# DVI_D_In.net
KiCad netlist of a schematic drawn in Altium Designer
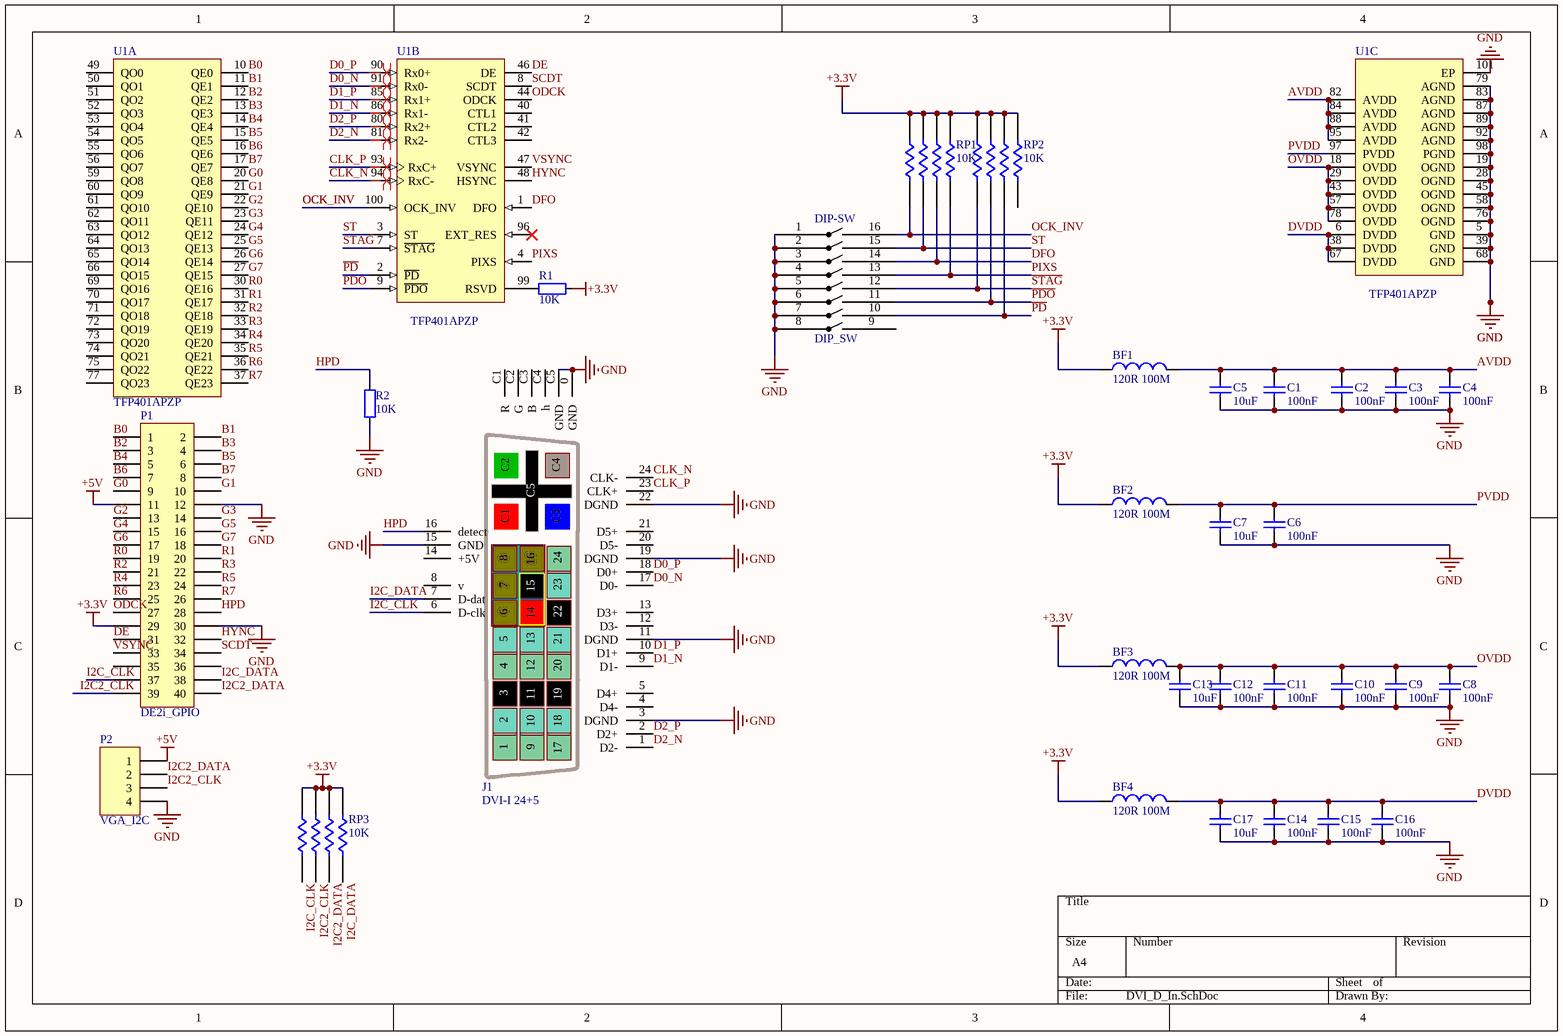
[diagram p0: DVI_D_In.SchDoc]

(export (version "E")
  (design (tool "Eeschema 10.0.6"))
  (components
    (comp (ref "BF1")
      (value "120R 100M")
      (footprint "L-1608[0603]")
      (fields (field (name "Comment") "GZ1608D121TF") (field (name "PUBLISHER") "Altium Limited"))
      (libsource (lib "Miscellaneous Devices") (part "Inductor"))
    )
    (comp (ref "BF2")
      (value "120R 100M")
      (footprint "L-1608[0603]")
      (fields (field (name "Comment") "GZ1608D121TF") (field (name "PUBLISHER") "Altium Limited"))
      (libsource (lib "Miscellaneous Devices") (part "Inductor"))
    )
    (comp (ref "BF3")
      (value "120R 100M")
      (footprint "L-1608[0603]")
      (fields (field (name "Comment") "GZ1608D121TF") (field (name "PUBLISHER") "Altium Limited"))
      (libsource (lib "Miscellaneous Devices") (part "Inductor"))
    )
    (comp (ref "BF4")
      (value "120R 100M")
      (footprint "L-1608[0603]")
      (fields (field (name "Comment") "GZ1608D121TF") (field (name "PUBLISHER") "Altium Limited"))
      (libsource (lib "Miscellaneous Devices") (part "Inductor"))
    )
    (comp (ref "C1")
      (value "100nF")
      (footprint "C-1608[0603]")
      (description "Capacitor (Semiconductor SIM Model)")
      (fields (field (name "Comment") "Cap Semi") (field (name "PUBLISHER") "Altium Limited"))
      (libsource (lib "Miscellaneous Devices") (part "Cap Semi"))
    )
    (comp (ref "C2")
      (value "100nF")
      (footprint "C-1608[0603]")
      (description "Capacitor (Semiconductor SIM Model)")
      (fields (field (name "Comment") "Cap Semi") (field (name "PUBLISHER") "Altium Limited"))
      (libsource (lib "Miscellaneous Devices") (part "Cap Semi"))
    )
    (comp (ref "C3")
      (value "100nF")
      (footprint "C-1608[0603]")
      (description "Capacitor (Semiconductor SIM Model)")
      (fields (field (name "Comment") "Cap Semi") (field (name "PUBLISHER") "Altium Limited"))
      (libsource (lib "Miscellaneous Devices") (part "Cap Semi"))
    )
    (comp (ref "C4")
      (value "100nF")
      (footprint "C-1608[0603]")
      (description "Capacitor (Semiconductor SIM Model)")
      (fields (field (name "Comment") "Cap Semi") (field (name "PUBLISHER") "Altium Limited"))
      (libsource (lib "Miscellaneous Devices") (part "Cap Semi"))
    )
    (comp (ref "C5")
      (value "10uF")
      (footprint "C-1608[0603]")
      (description "Capacitor (Semiconductor SIM Model)")
      (fields (field (name "Comment") "Cap Semi") (field (name "PUBLISHER") "Altium Limited"))
      (libsource (lib "Miscellaneous Devices") (part "Cap Semi"))
    )
    (comp (ref "C6")
      (value "100nF")
      (footprint "C-1608[0603]")
      (description "Capacitor (Semiconductor SIM Model)")
      (fields (field (name "Comment") "Cap Semi") (field (name "PUBLISHER") "Altium Limited"))
      (libsource (lib "Miscellaneous Devices") (part "Cap Semi"))
    )
    (comp (ref "C7")
      (value "10uF")
      (footprint "C-1608[0603]")
      (description "Capacitor (Semiconductor SIM Model)")
      (fields (field (name "Comment") "Cap Semi") (field (name "PUBLISHER") "Altium Limited"))
      (libsource (lib "Miscellaneous Devices") (part "Cap Semi"))
    )
    (comp (ref "C8")
      (value "100nF")
      (footprint "C-1608[0603]")
      (description "Capacitor (Semiconductor SIM Model)")
      (fields (field (name "Comment") "Cap Semi") (field (name "PUBLISHER") "Altium Limited"))
      (libsource (lib "Miscellaneous Devices") (part "Cap Semi"))
    )
    (comp (ref "C9")
      (value "100nF")
      (footprint "C-1608[0603]")
      (description "Capacitor (Semiconductor SIM Model)")
      (fields (field (name "Comment") "Cap Semi") (field (name "PUBLISHER") "Altium Limited"))
      (libsource (lib "Miscellaneous Devices") (part "Cap Semi"))
    )
    (comp (ref "C10")
      (value "100nF")
      (footprint "C-1608[0603]")
      (description "Capacitor (Semiconductor SIM Model)")
      (fields (field (name "Comment") "Cap Semi") (field (name "PUBLISHER") "Altium Limited"))
      (libsource (lib "Miscellaneous Devices") (part "Cap Semi"))
    )
    (comp (ref "C11")
      (value "100nF")
      (footprint "C-1608[0603]")
      (description "Capacitor (Semiconductor SIM Model)")
      (fields (field (name "Comment") "Cap Semi") (field (name "PUBLISHER") "Altium Limited"))
      (libsource (lib "Miscellaneous Devices") (part "Cap Semi"))
    )
    (comp (ref "C12")
      (value "100nF")
      (footprint "C-1608[0603]")
      (description "Capacitor (Semiconductor SIM Model)")
      (fields (field (name "Comment") "Cap Semi") (field (name "PUBLISHER") "Altium Limited"))
      (libsource (lib "Miscellaneous Devices") (part "Cap Semi"))
    )
    (comp (ref "C13")
      (value "10uF")
      (footprint "C-1608[0603]")
      (description "Capacitor (Semiconductor SIM Model)")
      (fields (field (name "Comment") "Cap Semi") (field (name "PUBLISHER") "Altium Limited"))
      (libsource (lib "Miscellaneous Devices") (part "Cap Semi"))
    )
    (comp (ref "C14")
      (value "100nF")
      (footprint "C-1608[0603]")
      (description "Capacitor (Semiconductor SIM Model)")
      (fields (field (name "Comment") "Cap Semi") (field (name "PUBLISHER") "Altium Limited"))
      (libsource (lib "Miscellaneous Devices") (part "Cap Semi"))
    )
    (comp (ref "C15")
      (value "100nF")
      (footprint "C-1608[0603]")
      (description "Capacitor (Semiconductor SIM Model)")
      (fields (field (name "Comment") "Cap Semi") (field (name "PUBLISHER") "Altium Limited"))
      (libsource (lib "Miscellaneous Devices") (part "Cap Semi"))
    )
    (comp (ref "C16")
      (value "100nF")
      (footprint "C-1608[0603]")
      (description "Capacitor (Semiconductor SIM Model)")
      (fields (field (name "Comment") "Cap Semi") (field (name "PUBLISHER") "Altium Limited"))
      (libsource (lib "Miscellaneous Devices") (part "Cap Semi"))
    )
    (comp (ref "C17")
      (value "10uF")
      (footprint "C-1608[0603]")
      (description "Capacitor (Semiconductor SIM Model)")
      (fields (field (name "Comment") "Cap Semi") (field (name "PUBLISHER") "Altium Limited"))
      (libsource (lib "Miscellaneous Devices") (part "Cap Semi"))
    )
    (comp (ref "DIP-SW") (value "DIP_SW") (footprint "SO16W") (libsource (lib "Schlib1") (part "DIP_SW")))
    (comp (ref "J1") (value "DVI-I 24+5") (footprint "DVI-I") (libsource (lib "DVI-I") (part "DVI-I")))
    (comp (ref "P1")
      (value "DE2i_GPIO")
      (footprint "HDR2X20")
      (description "Header, 20-Pin, Dual row")
      (fields (field (name "PUBLISHER") "Altium Limited"))
      (libsource (lib "Miscellaneous Connectors") (part "Header 20X2"))
    )
    (comp (ref "P2")
      (value "VGA_I2C")
      (footprint "HDR1X4H")
      (description "Header, 4-Pin, Right Angle")
      (fields (field (name "PUBLISHER") "Altium Limited"))
      (libsource (lib "Miscellaneous Connectors") (part "Header 4H"))
    )
    (comp (ref "R1")
      (value "10K")
      (footprint "PCB_PassiveRes:RES_0603")
      (description "Resistor")
      (fields (field (name "Comment") "Res_0603"))
      (libsource (lib "") (part "Res_0603_1"))
    )
    (comp (ref "R2")
      (value "10K")
      (footprint "PCB_PassiveRes:RES_0603")
      (description "Resistor")
      (fields (field (name "Comment") "Res_0603"))
      (libsource (lib "SCH_Passive") (part "Res_0603"))
    )
    (comp (ref "RP1") (value "10K") (footprint "R0603x4") (libsource (lib "general") (part "RPACK4")))
    (comp (ref "RP2") (value "10K") (footprint "R0603x4") (libsource (lib "general") (part "RPACK4")))
    (comp (ref "RP3") (value "10K") (footprint "R0603x4") (libsource (lib "general") (part "RPACK4")))
    (comp (ref "U1")
      (value "TFP401APZP")
      (footprint "PZP100-4700X4700TP_N")
      (fields (field (name "MANUFACTURER") "Texas Instruments"))
      (libsource (lib "Altium Content Vault") (part "CMP-0325-00069-1"))
    )
  )
  (nets
    (net (code "1") (name "+3.3V") (class "Default")
      (node (ref "BF1") (pin "1") (pinfunction "1_1") (pintype "passive"))
      (node (ref "BF2") (pin "1") (pinfunction "1_1") (pintype "passive"))
      (node (ref "BF3") (pin "1") (pinfunction "1_1") (pintype "passive"))
      (node (ref "BF4") (pin "1") (pinfunction "1_1") (pintype "passive"))
      (node (ref "P1") (pin "29") (pinfunction "29_29") (pintype "passive"))
      (node (ref "R1") (pin "2") (pinfunction "2_2") (pintype "passive"))
      (node (ref "RP1") (pin "5") (pinfunction "5_5") (pintype "passive"))
      (node (ref "RP1") (pin "6") (pinfunction "6_6") (pintype "passive"))
      (node (ref "RP1") (pin "7") (pinfunction "7_7") (pintype "passive"))
      (node (ref "RP1") (pin "8") (pinfunction "8_8") (pintype "passive"))
      (node (ref "RP2") (pin "5") (pinfunction "5_5") (pintype "passive"))
      (node (ref "RP2") (pin "6") (pinfunction "6_6") (pintype "passive"))
      (node (ref "RP2") (pin "7") (pinfunction "7_7") (pintype "passive"))
      (node (ref "RP2") (pin "8") (pinfunction "8_8") (pintype "passive"))
      (node (ref "RP3") (pin "5") (pinfunction "5_5") (pintype "passive"))
      (node (ref "RP3") (pin "6") (pinfunction "6_6") (pintype "passive"))
      (node (ref "RP3") (pin "7") (pinfunction "7_7") (pintype "passive"))
      (node (ref "RP3") (pin "8") (pinfunction "8_8") (pintype "passive"))
    )
    (net (code "2") (name "+5V") (class "Default")
      (node (ref "P1") (pin "11") (pinfunction "11_11") (pintype "passive"))
      (node (ref "P2") (pin "1") (pinfunction "1_1") (pintype "passive"))
    )
    (net (code "3") (name "/AVDD") (class "Default")
      (node (ref "BF1") (pin "2") (pinfunction "2_2") (pintype "passive"))
      (node (ref "C1") (pin "2") (pinfunction "2_2") (pintype "passive"))
      (node (ref "C2") (pin "2") (pinfunction "2_2") (pintype "passive"))
      (node (ref "C3") (pin "2") (pinfunction "2_2") (pintype "passive"))
      (node (ref "C4") (pin "2") (pinfunction "2_2") (pintype "passive"))
      (node (ref "C5") (pin "2") (pinfunction "2_2") (pintype "passive"))
      (node (ref "U1") (pin "82") (pinfunction "AVDD_82") (pintype "power_in"))
      (node (ref "U1") (pin "84") (pinfunction "AVDD_84") (pintype "power_in"))
      (node (ref "U1") (pin "88") (pinfunction "AVDD_88") (pintype "power_in"))
      (node (ref "U1") (pin "95") (pinfunction "AVDD_95") (pintype "power_in"))
    )
    (net (code "4") (name "/B0") (class "Default")
      (node (ref "P1") (pin "1") (pinfunction "1_1") (pintype "passive"))
      (node (ref "U1") (pin "10") (pinfunction "QE0_10") (pintype "tri_state"))
    )
    (net (code "5") (name "/B1") (class "Default")
      (node (ref "P1") (pin "2") (pinfunction "2_2") (pintype "passive"))
      (node (ref "U1") (pin "11") (pinfunction "QE1_11") (pintype "tri_state"))
    )
    (net (code "6") (name "/B2") (class "Default")
      (node (ref "P1") (pin "3") (pinfunction "3_3") (pintype "passive"))
      (node (ref "U1") (pin "12") (pinfunction "QE2_12") (pintype "tri_state"))
    )
    (net (code "7") (name "/B3") (class "Default")
      (node (ref "P1") (pin "4") (pinfunction "4_4") (pintype "passive"))
      (node (ref "U1") (pin "13") (pinfunction "QE3_13") (pintype "tri_state"))
    )
    (net (code "8") (name "/B4") (class "Default")
      (node (ref "P1") (pin "5") (pinfunction "5_5") (pintype "passive"))
      (node (ref "U1") (pin "14") (pinfunction "QE4_14") (pintype "tri_state"))
    )
    (net (code "9") (name "/B5") (class "Default")
      (node (ref "P1") (pin "6") (pinfunction "6_6") (pintype "passive"))
      (node (ref "U1") (pin "15") (pinfunction "QE5_15") (pintype "tri_state"))
    )
    (net (code "10") (name "/B6") (class "Default")
      (node (ref "P1") (pin "7") (pinfunction "7_7") (pintype "passive"))
      (node (ref "U1") (pin "16") (pinfunction "QE6_16") (pintype "tri_state"))
    )
    (net (code "11") (name "/B7") (class "Default")
      (node (ref "P1") (pin "8") (pinfunction "8_8") (pintype "passive"))
      (node (ref "U1") (pin "17") (pinfunction "QE7_17") (pintype "tri_state"))
    )
    (net (code "12") (name "/CLK_N") (class "Default")
      (node (ref "J1") (pin "24") (pinfunction "CLK-_24") (pintype "passive"))
      (node (ref "U1") (pin "94") (pinfunction "RxC-_94") (pintype "input"))
    )
    (net (code "13") (name "/CLK_P") (class "Default")
      (node (ref "J1") (pin "23") (pinfunction "CLK+_23") (pintype "passive"))
      (node (ref "U1") (pin "93") (pinfunction "RxC+_93") (pintype "input"))
    )
    (net (code "14") (name "/D0_N") (class "Default")
      (node (ref "J1") (pin "17") (pinfunction "D0-_17") (pintype "passive"))
      (node (ref "U1") (pin "91") (pinfunction "Rx0-_91") (pintype "input"))
    )
    (net (code "15") (name "/D0_P") (class "Default")
      (node (ref "J1") (pin "18") (pinfunction "D0+_18") (pintype "passive"))
      (node (ref "U1") (pin "90") (pinfunction "Rx0+_90") (pintype "input"))
    )
    (net (code "16") (name "/D1_N") (class "Default")
      (node (ref "J1") (pin "9") (pinfunction "D1-_9") (pintype "passive"))
      (node (ref "U1") (pin "86") (pinfunction "Rx1-_86") (pintype "input"))
    )
    (net (code "17") (name "/D1_P") (class "Default")
      (node (ref "J1") (pin "10") (pinfunction "D1+_10") (pintype "passive"))
      (node (ref "U1") (pin "85") (pinfunction "Rx1+_85") (pintype "input"))
    )
    (net (code "18") (name "/D2_N") (class "Default")
      (node (ref "J1") (pin "1") (pinfunction "D2-_1") (pintype "passive"))
      (node (ref "U1") (pin "81") (pinfunction "Rx2-_81") (pintype "input"))
    )
    (net (code "19") (name "/D2_P") (class "Default")
      (node (ref "J1") (pin "2") (pinfunction "D2+_2") (pintype "passive"))
      (node (ref "U1") (pin "80") (pinfunction "Rx2+_80") (pintype "input"))
    )
    (net (code "20") (name "/DE") (class "Default")
      (node (ref "P1") (pin "31") (pinfunction "31_31") (pintype "passive"))
      (node (ref "U1") (pin "46") (pinfunction "DE_46") (pintype "tri_state"))
    )
    (net (code "21") (name "/DFO") (class "Default")
      (node (ref "DIP-SW") (pin "14") (pinfunction "14_14") (pintype "passive"))
      (node (ref "RP1") (pin "3") (pinfunction "3_3") (pintype "passive"))
      (node (ref "U1") (pin "1") (pinfunction "DFO_1") (pintype "input"))
    )
    (net (code "22") (name "/DVDD") (class "Default")
      (node (ref "BF4") (pin "2") (pinfunction "2_2") (pintype "passive"))
      (node (ref "C14") (pin "2") (pinfunction "2_2") (pintype "passive"))
      (node (ref "C15") (pin "2") (pinfunction "2_2") (pintype "passive"))
      (node (ref "C16") (pin "2") (pinfunction "2_2") (pintype "passive"))
      (node (ref "C17") (pin "2") (pinfunction "2_2") (pintype "passive"))
      (node (ref "U1") (pin "38") (pinfunction "DVDD_38") (pintype "power_in"))
      (node (ref "U1") (pin "6") (pinfunction "DVDD_6") (pintype "power_in"))
      (node (ref "U1") (pin "67") (pinfunction "DVDD_67") (pintype "power_in"))
    )
    (net (code "23") (name "/G0") (class "Default")
      (node (ref "P1") (pin "9") (pinfunction "9_9") (pintype "passive"))
      (node (ref "U1") (pin "20") (pinfunction "QE8_20") (pintype "tri_state"))
    )
    (net (code "24") (name "/G1") (class "Default")
      (node (ref "P1") (pin "10") (pinfunction "10_10") (pintype "passive"))
      (node (ref "U1") (pin "21") (pinfunction "QE9_21") (pintype "tri_state"))
    )
    (net (code "25") (name "/G2") (class "Default")
      (node (ref "P1") (pin "13") (pinfunction "13_13") (pintype "passive"))
      (node (ref "U1") (pin "22") (pinfunction "QE10_22") (pintype "tri_state"))
    )
    (net (code "26") (name "/G3") (class "Default")
      (node (ref "P1") (pin "14") (pinfunction "14_14") (pintype "passive"))
      (node (ref "U1") (pin "23") (pinfunction "QE11_23") (pintype "tri_state"))
    )
    (net (code "27") (name "/G4") (class "Default")
      (node (ref "P1") (pin "15") (pinfunction "15_15") (pintype "passive"))
      (node (ref "U1") (pin "24") (pinfunction "QE12_24") (pintype "tri_state"))
    )
    (net (code "28") (name "/G5") (class "Default")
      (node (ref "P1") (pin "16") (pinfunction "16_16") (pintype "passive"))
      (node (ref "U1") (pin "25") (pinfunction "QE13_25") (pintype "tri_state"))
    )
    (net (code "29") (name "/G6") (class "Default")
      (node (ref "P1") (pin "17") (pinfunction "17_17") (pintype "passive"))
      (node (ref "U1") (pin "26") (pinfunction "QE14_26") (pintype "tri_state"))
    )
    (net (code "30") (name "/G7") (class "Default")
      (node (ref "P1") (pin "18") (pinfunction "18_18") (pintype "passive"))
      (node (ref "U1") (pin "27") (pinfunction "QE15_27") (pintype "tri_state"))
    )
    (net (code "31") (name "/HPD") (class "Default")
      (node (ref "J1") (pin "16") (pinfunction "detect_16") (pintype "passive"))
      (node (ref "P1") (pin "28") (pinfunction "28_28") (pintype "passive"))
      (node (ref "R2") (pin "2") (pinfunction "2_2") (pintype "passive"))
    )
    (net (code "32") (name "/HYNC") (class "Default")
      (node (ref "P1") (pin "32") (pinfunction "32_32") (pintype "passive"))
      (node (ref "U1") (pin "48") (pinfunction "HSYNC_48") (pintype "tri_state"))
    )
    (net (code "33") (name "/I2C2_CLK") (class "Default")
      (node (ref "P1") (pin "39") (pinfunction "39_39") (pintype "passive"))
      (node (ref "P2") (pin "3") (pinfunction "3_3") (pintype "passive"))
      (node (ref "RP3") (pin "2") (pinfunction "2_2") (pintype "passive"))
    )
    (net (code "34") (name "/I2C2_DATA") (class "Default")
      (node (ref "P1") (pin "40") (pinfunction "40_40") (pintype "passive"))
      (node (ref "P2") (pin "2") (pinfunction "2_2") (pintype "passive"))
      (node (ref "RP3") (pin "3") (pinfunction "3_3") (pintype "passive"))
    )
    (net (code "35") (name "/I2C_CLK") (class "Default")
      (node (ref "J1") (pin "6") (pinfunction "D-clk_6") (pintype "passive"))
      (node (ref "P1") (pin "37") (pinfunction "37_37") (pintype "passive"))
      (node (ref "RP3") (pin "1") (pinfunction "1_1") (pintype "passive"))
    )
    (net (code "36") (name "/I2C_DATA") (class "Default")
      (node (ref "J1") (pin "7") (pinfunction "D-dat_7") (pintype "passive"))
      (node (ref "P1") (pin "38") (pinfunction "38_38") (pintype "passive"))
      (node (ref "RP3") (pin "4") (pinfunction "4_4") (pintype "passive"))
    )
    (net (code "37") (name "/OCK_INV") (class "Default")
      (node (ref "DIP-SW") (pin "16") (pinfunction "16_16") (pintype "passive"))
      (node (ref "RP1") (pin "1") (pinfunction "1_1") (pintype "passive"))
      (node (ref "U1") (pin "100") (pinfunction "OCK_INV_100") (pintype "input"))
    )
    (net (code "38") (name "/ODCK") (class "Default")
      (node (ref "P1") (pin "27") (pinfunction "27_27") (pintype "passive"))
      (node (ref "U1") (pin "44") (pinfunction "ODCK_44") (pintype "tri_state"))
    )
    (net (code "39") (name "/OVDD") (class "Default")
      (node (ref "BF3") (pin "2") (pinfunction "2_2") (pintype "passive"))
      (node (ref "C10") (pin "2") (pinfunction "2_2") (pintype "passive"))
      (node (ref "C11") (pin "2") (pinfunction "2_2") (pintype "passive"))
      (node (ref "C12") (pin "2") (pinfunction "2_2") (pintype "passive"))
      (node (ref "C13") (pin "2") (pinfunction "2_2") (pintype "passive"))
      (node (ref "C8") (pin "2") (pinfunction "2_2") (pintype "passive"))
      (node (ref "C9") (pin "2") (pinfunction "2_2") (pintype "passive"))
      (node (ref "U1") (pin "18") (pinfunction "OVDD_18") (pintype "power_in"))
      (node (ref "U1") (pin "29") (pinfunction "OVDD_29") (pintype "power_in"))
      (node (ref "U1") (pin "43") (pinfunction "OVDD_43") (pintype "power_in"))
      (node (ref "U1") (pin "57") (pinfunction "OVDD_57") (pintype "power_in"))
      (node (ref "U1") (pin "78") (pinfunction "OVDD_78") (pintype "power_in"))
    )
    (net (code "40") (name "/PIXS") (class "Default")
      (node (ref "DIP-SW") (pin "13") (pinfunction "13_13") (pintype "passive"))
      (node (ref "RP1") (pin "4") (pinfunction "4_4") (pintype "passive"))
      (node (ref "U1") (pin "4") (pinfunction "PIXS_4") (pintype "input"))
    )
    (net (code "41") (name "/PVDD") (class "Default")
      (node (ref "BF2") (pin "2") (pinfunction "2_2") (pintype "passive"))
      (node (ref "C6") (pin "2") (pinfunction "2_2") (pintype "passive"))
      (node (ref "C7") (pin "2") (pinfunction "2_2") (pintype "passive"))
      (node (ref "U1") (pin "97") (pinfunction "PVDD_97") (pintype "power_in"))
    )
    (net (code "42") (name "/R0") (class "Default")
      (node (ref "P1") (pin "19") (pinfunction "19_19") (pintype "passive"))
      (node (ref "U1") (pin "30") (pinfunction "QE16_30") (pintype "tri_state"))
    )
    (net (code "43") (name "/R1") (class "Default")
      (node (ref "P1") (pin "20") (pinfunction "20_20") (pintype "passive"))
      (node (ref "U1") (pin "31") (pinfunction "QE17_31") (pintype "tri_state"))
    )
    (net (code "44") (name "/R2") (class "Default")
      (node (ref "P1") (pin "21") (pinfunction "21_21") (pintype "passive"))
      (node (ref "U1") (pin "32") (pinfunction "QE18_32") (pintype "tri_state"))
    )
    (net (code "45") (name "/R3") (class "Default")
      (node (ref "P1") (pin "22") (pinfunction "22_22") (pintype "passive"))
      (node (ref "U1") (pin "33") (pinfunction "QE19_33") (pintype "tri_state"))
    )
    (net (code "46") (name "/R4") (class "Default")
      (node (ref "P1") (pin "23") (pinfunction "23_23") (pintype "passive"))
      (node (ref "U1") (pin "34") (pinfunction "QE20_34") (pintype "tri_state"))
    )
    (net (code "47") (name "/R5") (class "Default")
      (node (ref "P1") (pin "24") (pinfunction "24_24") (pintype "passive"))
      (node (ref "U1") (pin "35") (pinfunction "QE21_35") (pintype "tri_state"))
    )
    (net (code "48") (name "/R6") (class "Default")
      (node (ref "P1") (pin "25") (pinfunction "25_25") (pintype "passive"))
      (node (ref "U1") (pin "36") (pinfunction "QE22_36") (pintype "tri_state"))
    )
    (net (code "49") (name "/R7") (class "Default")
      (node (ref "P1") (pin "26") (pinfunction "26_26") (pintype "passive"))
      (node (ref "U1") (pin "37") (pinfunction "QE23_37") (pintype "tri_state"))
    )
    (net (code "50") (name "/SCDT") (class "Default")
      (node (ref "P1") (pin "34") (pinfunction "34_34") (pintype "passive"))
      (node (ref "U1") (pin "8") (pinfunction "SCDT_8") (pintype "tri_state"))
    )
    (net (code "51") (name "/ST") (class "Default")
      (node (ref "DIP-SW") (pin "15") (pinfunction "15_15") (pintype "passive"))
      (node (ref "RP1") (pin "2") (pinfunction "2_2") (pintype "passive"))
      (node (ref "U1") (pin "3") (pinfunction "ST_3") (pintype "input"))
    )
    (net (code "52") (name "/VSYNC") (class "Default")
      (node (ref "P1") (pin "33") (pinfunction "33_33") (pintype "passive"))
      (node (ref "U1") (pin "47") (pinfunction "VSYNC_47") (pintype "tri_state"))
    )
    (net (code "53") (name "/~{PDO}") (class "Default")
      (node (ref "DIP-SW") (pin "11") (pinfunction "11_11") (pintype "passive"))
      (node (ref "RP2") (pin "2") (pinfunction "2_2") (pintype "passive"))
      (node (ref "U1") (pin "9") (pinfunction "~{PDO}_9") (pintype "input"))
    )
    (net (code "54") (name "/~{PD}") (class "Default")
      (node (ref "DIP-SW") (pin "10") (pinfunction "10_10") (pintype "passive"))
      (node (ref "RP2") (pin "3") (pinfunction "3_3") (pintype "passive"))
      (node (ref "U1") (pin "2") (pinfunction "~{PD}_2") (pintype "input"))
    )
    (net (code "55") (name "/~{STAG}") (class "Default")
      (node (ref "DIP-SW") (pin "12") (pinfunction "12_12") (pintype "passive"))
      (node (ref "RP2") (pin "1") (pinfunction "1_1") (pintype "passive"))
      (node (ref "U1") (pin "7") (pinfunction "~{STAG}_7") (pintype "input"))
    )
    (net (code "56") (name "GND") (class "Default")
      (node (ref "C1") (pin "1") (pinfunction "1_1") (pintype "passive"))
      (node (ref "C10") (pin "1") (pinfunction "1_1") (pintype "passive"))
      (node (ref "C11") (pin "1") (pinfunction "1_1") (pintype "passive"))
      (node (ref "C12") (pin "1") (pinfunction "1_1") (pintype "passive"))
      (node (ref "C13") (pin "1") (pinfunction "1_1") (pintype "passive"))
      (node (ref "C14") (pin "1") (pinfunction "1_1") (pintype "passive"))
      (node (ref "C15") (pin "1") (pinfunction "1_1") (pintype "passive"))
      (node (ref "C16") (pin "1") (pinfunction "1_1") (pintype "passive"))
      (node (ref "C17") (pin "1") (pinfunction "1_1") (pintype "passive"))
      (node (ref "C2") (pin "1") (pinfunction "1_1") (pintype "passive"))
      (node (ref "C3") (pin "1") (pinfunction "1_1") (pintype "passive"))
      (node (ref "C4") (pin "1") (pinfunction "1_1") (pintype "passive"))
      (node (ref "C5") (pin "1") (pinfunction "1_1") (pintype "passive"))
      (node (ref "C6") (pin "1") (pinfunction "1_1") (pintype "passive"))
      (node (ref "C7") (pin "1") (pinfunction "1_1") (pintype "passive"))
      (node (ref "C8") (pin "1") (pinfunction "1_1") (pintype "passive"))
      (node (ref "C9") (pin "1") (pinfunction "1_1") (pintype "passive"))
      (node (ref "DIP-SW") (pin "1") (pinfunction "1_1") (pintype "passive"))
      (node (ref "DIP-SW") (pin "2") (pinfunction "2_2") (pintype "passive"))
      (node (ref "DIP-SW") (pin "3") (pinfunction "3_3") (pintype "passive"))
      (node (ref "DIP-SW") (pin "4") (pinfunction "4_4") (pintype "passive"))
      (node (ref "DIP-SW") (pin "5") (pinfunction "5_5") (pintype "passive"))
      (node (ref "DIP-SW") (pin "6") (pinfunction "6_6") (pintype "passive"))
      (node (ref "DIP-SW") (pin "7") (pinfunction "7_7") (pintype "passive"))
      (node (ref "DIP-SW") (pin "8") (pinfunction "8_8") (pintype "passive"))
      (node (ref "J1") (pin "0") (pinfunction "GND_0") (pintype "passive"))
      (node (ref "J1") (pin "11") (pinfunction "DGND_11") (pintype "passive"))
      (node (ref "J1") (pin "15") (pinfunction "GND_15") (pintype "passive"))
      (node (ref "J1") (pin "19") (pinfunction "DGND_19") (pintype "passive"))
      (node (ref "J1") (pin "22") (pinfunction "DGND_22") (pintype "passive"))
      (node (ref "J1") (pin "3") (pinfunction "DGND_3") (pintype "passive"))
      (node (ref "J1") (pin "C5") (pinfunction "GND_C5") (pintype "passive"))
      (node (ref "P1") (pin "12") (pinfunction "12_12") (pintype "passive"))
      (node (ref "P1") (pin "30") (pinfunction "30_30") (pintype "passive"))
      (node (ref "P2") (pin "4") (pinfunction "4_4") (pintype "passive"))
      (node (ref "R2") (pin "1") (pinfunction "1_1") (pintype "passive"))
      (node (ref "U1") (pin "101") (pinfunction "EP_101") (pintype "passive"))
      (node (ref "U1") (pin "19") (pinfunction "OGND_19") (pintype "power_in"))
      (node (ref "U1") (pin "28") (pinfunction "OGND_28") (pintype "power_in"))
      (node (ref "U1") (pin "39") (pinfunction "GND_39") (pintype "power_in"))
      (node (ref "U1") (pin "45") (pinfunction "OGND_45") (pintype "power_in"))
      (node (ref "U1") (pin "5") (pinfunction "GND_5") (pintype "power_in"))
      (node (ref "U1") (pin "58") (pinfunction "OGND_58") (pintype "power_in"))
      (node (ref "U1") (pin "68") (pinfunction "GND_68") (pintype "power_in"))
      (node (ref "U1") (pin "76") (pinfunction "OGND_76") (pintype "power_in"))
      (node (ref "U1") (pin "79") (pinfunction "AGND_79") (pintype "power_in"))
      (node (ref "U1") (pin "83") (pinfunction "AGND_83") (pintype "power_in"))
      (node (ref "U1") (pin "87") (pinfunction "AGND_87") (pintype "power_in"))
      (node (ref "U1") (pin "89") (pinfunction "AGND_89") (pintype "power_in"))
      (node (ref "U1") (pin "92") (pinfunction "AGND_92") (pintype "power_in"))
      (node (ref "U1") (pin "98") (pinfunction "PGND_98") (pintype "power_in"))
    )
    (net (code "57") (name "Net-(U1B-RSVD)") (class "Default")
      (node (ref "R1") (pin "1") (pinfunction "1_1") (pintype "passive"))
      (node (ref "U1") (pin "99") (pinfunction "RSVD_99") (pintype "passive"))
    )
    (net (code "58") (name "unconnected-(DIP-SW-Pad9)") (class "Default")
      (node (ref "DIP-SW") (pin "9") (pinfunction "9_9") (pintype "passive"))
    )
    (net (code "59") (name "unconnected-(J1-+5V-Pad14)") (class "Default")
      (node (ref "J1") (pin "14") (pinfunction "+5V_14") (pintype "passive"))
    )
    (net (code "60") (name "unconnected-(J1-B-PadC3)") (class "Default")
      (node (ref "J1") (pin "C3") (pinfunction "B_C3") (pintype "passive"))
    )
    (net (code "61") (name "unconnected-(J1-D3+-Pad13)") (class "Default")
      (node (ref "J1") (pin "13") (pinfunction "D3+_13") (pintype "passive"))
    )
    (net (code "62") (name "unconnected-(J1-D3--Pad12)") (class "Default")
      (node (ref "J1") (pin "12") (pinfunction "D3-_12") (pintype "passive"))
    )
    (net (code "63") (name "unconnected-(J1-D4+-Pad5)") (class "Default")
      (node (ref "J1") (pin "5") (pinfunction "D4+_5") (pintype "passive"))
    )
    (net (code "64") (name "unconnected-(J1-D4--Pad4)") (class "Default")
      (node (ref "J1") (pin "4") (pinfunction "D4-_4") (pintype "passive"))
    )
    (net (code "65") (name "unconnected-(J1-D5+-Pad21)") (class "Default")
      (node (ref "J1") (pin "21") (pinfunction "D5+_21") (pintype "passive"))
    )
    (net (code "66") (name "unconnected-(J1-D5--Pad20)") (class "Default")
      (node (ref "J1") (pin "20") (pinfunction "D5-_20") (pintype "passive"))
    )
    (net (code "67") (name "unconnected-(J1-G-PadC2)") (class "Default")
      (node (ref "J1") (pin "C2") (pinfunction "G_C2") (pintype "passive"))
    )
    (net (code "68") (name "unconnected-(J1-R-PadC1)") (class "Default")
      (node (ref "J1") (pin "C1") (pinfunction "R_C1") (pintype "passive"))
    )
    (net (code "69") (name "unconnected-(J1-h-PadC4)") (class "Default")
      (node (ref "J1") (pin "C4") (pinfunction "h_C4") (pintype "passive"))
    )
    (net (code "70") (name "unconnected-(J1-v-Pad8)") (class "Default")
      (node (ref "J1") (pin "8") (pinfunction "v_8") (pintype "passive"))
    )
    (net (code "71") (name "unconnected-(P1-Pad35)") (class "Default")
      (node (ref "P1") (pin "35") (pinfunction "35_35") (pintype "passive"))
    )
    (net (code "72") (name "unconnected-(P1-Pad36)") (class "Default")
      (node (ref "P1") (pin "36") (pinfunction "36_36") (pintype "passive"))
    )
    (net (code "73") (name "unconnected-(RP2-Pad4)") (class "Default")
      (node (ref "RP2") (pin "4") (pinfunction "4_4") (pintype "passive"))
    )
    (net (code "74") (name "unconnected-(U1A-QO0-Pad49)") (class "Default")
      (node (ref "U1") (pin "49") (pinfunction "QO0_49") (pintype "tri_state"))
    )
    (net (code "75") (name "unconnected-(U1A-QO1-Pad50)") (class "Default")
      (node (ref "U1") (pin "50") (pinfunction "QO1_50") (pintype "tri_state"))
    )
    (net (code "76") (name "unconnected-(U1A-QO2-Pad51)") (class "Default")
      (node (ref "U1") (pin "51") (pinfunction "QO2_51") (pintype "tri_state"))
    )
    (net (code "77") (name "unconnected-(U1A-QO3-Pad52)") (class "Default")
      (node (ref "U1") (pin "52") (pinfunction "QO3_52") (pintype "tri_state"))
    )
    (net (code "78") (name "unconnected-(U1A-QO4-Pad53)") (class "Default")
      (node (ref "U1") (pin "53") (pinfunction "QO4_53") (pintype "tri_state"))
    )
    (net (code "79") (name "unconnected-(U1A-QO5-Pad54)") (class "Default")
      (node (ref "U1") (pin "54") (pinfunction "QO5_54") (pintype "tri_state"))
    )
    (net (code "80") (name "unconnected-(U1A-QO6-Pad55)") (class "Default")
      (node (ref "U1") (pin "55") (pinfunction "QO6_55") (pintype "tri_state"))
    )
    (net (code "81") (name "unconnected-(U1A-QO7-Pad56)") (class "Default")
      (node (ref "U1") (pin "56") (pinfunction "QO7_56") (pintype "tri_state"))
    )
    (net (code "82") (name "unconnected-(U1A-QO8-Pad59)") (class "Default")
      (node (ref "U1") (pin "59") (pinfunction "QO8_59") (pintype "tri_state"))
    )
    (net (code "83") (name "unconnected-(U1A-QO9-Pad60)") (class "Default")
      (node (ref "U1") (pin "60") (pinfunction "QO9_60") (pintype "tri_state"))
    )
    (net (code "84") (name "unconnected-(U1A-QO10-Pad61)") (class "Default")
      (node (ref "U1") (pin "61") (pinfunction "QO10_61") (pintype "tri_state"))
    )
    (net (code "85") (name "unconnected-(U1A-QO11-Pad62)") (class "Default")
      (node (ref "U1") (pin "62") (pinfunction "QO11_62") (pintype "tri_state"))
    )
    (net (code "86") (name "unconnected-(U1A-QO12-Pad63)") (class "Default")
      (node (ref "U1") (pin "63") (pinfunction "QO12_63") (pintype "tri_state"))
    )
    (net (code "87") (name "unconnected-(U1A-QO13-Pad64)") (class "Default")
      (node (ref "U1") (pin "64") (pinfunction "QO13_64") (pintype "tri_state"))
    )
    (net (code "88") (name "unconnected-(U1A-QO14-Pad65)") (class "Default")
      (node (ref "U1") (pin "65") (pinfunction "QO14_65") (pintype "tri_state"))
    )
    (net (code "89") (name "unconnected-(U1A-QO15-Pad66)") (class "Default")
      (node (ref "U1") (pin "66") (pinfunction "QO15_66") (pintype "tri_state"))
    )
    (net (code "90") (name "unconnected-(U1A-QO16-Pad69)") (class "Default")
      (node (ref "U1") (pin "69") (pinfunction "QO16_69") (pintype "tri_state"))
    )
    (net (code "91") (name "unconnected-(U1A-QO17-Pad70)") (class "Default")
      (node (ref "U1") (pin "70") (pinfunction "QO17_70") (pintype "tri_state"))
    )
    (net (code "92") (name "unconnected-(U1A-QO18-Pad71)") (class "Default")
      (node (ref "U1") (pin "71") (pinfunction "QO18_71") (pintype "tri_state"))
    )
    (net (code "93") (name "unconnected-(U1A-QO19-Pad72)") (class "Default")
      (node (ref "U1") (pin "72") (pinfunction "QO19_72") (pintype "tri_state"))
    )
    (net (code "94") (name "unconnected-(U1A-QO20-Pad73)") (class "Default")
      (node (ref "U1") (pin "73") (pinfunction "QO20_73") (pintype "tri_state"))
    )
    (net (code "95") (name "unconnected-(U1A-QO21-Pad74)") (class "Default")
      (node (ref "U1") (pin "74") (pinfunction "QO21_74") (pintype "tri_state"))
    )
    (net (code "96") (name "unconnected-(U1A-QO22-Pad75)") (class "Default")
      (node (ref "U1") (pin "75") (pinfunction "QO22_75") (pintype "tri_state"))
    )
    (net (code "97") (name "unconnected-(U1A-QO23-Pad77)") (class "Default")
      (node (ref "U1") (pin "77") (pinfunction "QO23_77") (pintype "tri_state"))
    )
    (net (code "98") (name "unconnected-(U1B-CTL1-Pad40)") (class "Default")
      (node (ref "U1") (pin "40") (pinfunction "CTL1_40") (pintype "tri_state"))
    )
    (net (code "99") (name "unconnected-(U1B-CTL2-Pad41)") (class "Default")
      (node (ref "U1") (pin "41") (pinfunction "CTL2_41") (pintype "tri_state"))
    )
    (net (code "100") (name "unconnected-(U1B-CTL3-Pad42)") (class "Default")
      (node (ref "U1") (pin "42") (pinfunction "CTL3_42") (pintype "tri_state"))
    )
    (net (code "101") (name "unconnected-(U1B-EXT_RES-Pad96)") (class "Default")
      (node (ref "U1") (pin "96") (pinfunction "EXT_RES_96") (pintype "input+no_connect"))
    )
  )
)
